# LED_Inducator.net
KiCad netlist of a schematic drawn in Altium Designer
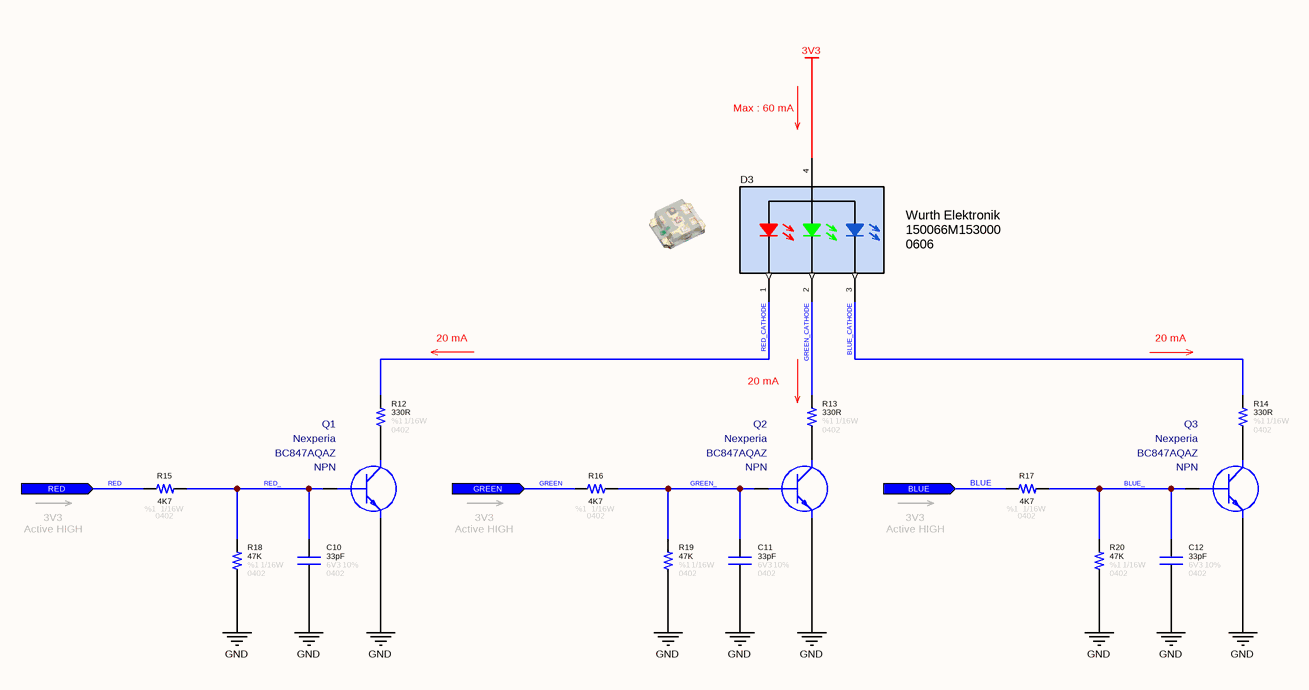
[diagram p0: LED Inducator.SchDoc]

(export (version "E")
  (design (tool "Eeschema 10.0.6"))
  (components
    (comp (ref "C10")
      (value "33pF")
      (footprint "CAPACITOR_0402")
      (description "Capacitor - 33pF [0402] (Ceramic)")
      (fields
        (field (name "MANUFACTURER PART NUMBER") "C0402C330J9RACAUTO")
        (field (name "TOLERANCE") "10%")
        (field (name "CASE") "0402")
        (field (name "VOLTAGE") "6V3")
      )
      (libsource (lib "Akkoyun") (part "Capacitor - 33pF [0402-6V3]"))
    )
    (comp (ref "C11")
      (value "33pF")
      (footprint "CAPACITOR_0402")
      (description "Capacitor - 33pF [0402] (Ceramic)")
      (fields
        (field (name "MANUFACTURER PART NUMBER") "C0402C330J9RACAUTO")
        (field (name "TOLERANCE") "10%")
        (field (name "CASE") "0402")
        (field (name "VOLTAGE") "6V3")
      )
      (libsource (lib "Akkoyun") (part "Capacitor - 33pF [0402-6V3]"))
    )
    (comp (ref "C12")
      (value "33pF")
      (footprint "CAPACITOR_0402")
      (description "Capacitor - 33pF [0402] (Ceramic)")
      (fields
        (field (name "MANUFACTURER PART NUMBER") "C0402C330J9RACAUTO")
        (field (name "TOLERANCE") "10%")
        (field (name "CASE") "0402")
        (field (name "VOLTAGE") "6V3")
      )
      (libsource (lib "Akkoyun") (part "Capacitor - 33pF [0402-6V3]"))
    )
    (comp (ref "D3")
      (value "~")
      (footprint "Wurth_0606")
      (description "LED RGB DIFFUSED SMD")
      (fields
        (field (name "MANUFACTURER NAME") "Wurth Elektronik")
        (field (name "MANUFACTURER PART NUMBER") "150066M153000")
        (field (name "CASE") "0606")
      )
      (libsource (lib "Akkoyun") (part "Diode - LED-RGB"))
    )
    (comp (ref "Q1")
      (value "~")
      (footprint "SOT1215")
      (description "Bipolar NPN Transistors")
      (fields
        (field (name "MANUFACTURER NAME") "Nexperia")
        (field (name "MANUFACTURER PART NUMBER") "BC847AQAZ")
        (field (name "POLARITY") "NPN")
      )
      (libsource (lib "Akkoyun") (part "Transistor - BC847"))
    )
    (comp (ref "Q2")
      (value "~")
      (footprint "SOT1215")
      (description "Bipolar NPN Transistors")
      (fields
        (field (name "MANUFACTURER NAME") "Nexperia")
        (field (name "MANUFACTURER PART NUMBER") "BC847AQAZ")
        (field (name "POLARITY") "NPN")
      )
      (libsource (lib "Akkoyun") (part "Transistor - BC847"))
    )
    (comp (ref "Q3")
      (value "~")
      (footprint "SOT1215")
      (description "Bipolar NPN Transistors")
      (fields
        (field (name "MANUFACTURER NAME") "Nexperia")
        (field (name "MANUFACTURER PART NUMBER") "BC847AQAZ")
        (field (name "POLARITY") "NPN")
      )
      (libsource (lib "Akkoyun") (part "Transistor - BC847"))
    )
    (comp (ref "R12")
      (value "330R")
      (footprint "RESISTOR_0402")
      (description "Thick Film Resistors - SMD 1/16 W 330 Ohm 1%")
      (fields
        (field (name "MANUFACTURER PART NUMBER") "CRCW0402330RFKED")
        (field (name "CASE") "0402")
        (field (name "TOLERANCE") "%1")
        (field (name "POWER") "1/16W")
      )
      (libsource (lib "Akkoyun") (part "Resistor - 330R [0402]"))
    )
    (comp (ref "R13")
      (value "330R")
      (footprint "RESISTOR_0402")
      (description "Thick Film Resistors - SMD 1/16 W 330 Ohm 1%")
      (fields
        (field (name "MANUFACTURER PART NUMBER") "CRCW0402330RFKED")
        (field (name "CASE") "0402")
        (field (name "TOLERANCE") "%1")
        (field (name "POWER") "1/16W")
      )
      (libsource (lib "Akkoyun") (part "Resistor - 330R [0402]"))
    )
    (comp (ref "R14")
      (value "330R")
      (footprint "RESISTOR_0402")
      (description "Thick Film Resistors - SMD 1/16 W 330 Ohm 1%")
      (fields
        (field (name "MANUFACTURER PART NUMBER") "CRCW0402330RFKED")
        (field (name "CASE") "0402")
        (field (name "TOLERANCE") "%1")
        (field (name "POWER") "1/16W")
      )
      (libsource (lib "Akkoyun") (part "Resistor - 330R [0402]"))
    )
    (comp (ref "R15")
      (value "4K7")
      (footprint "RESISTOR_0402")
      (description "Thick Film Resistors - SMD 1/16 W 4.7 KOhm 1%")
      (fields
        (field (name "MANUFACTURER PART NUMBER") "CRCW04024K70FKED")
        (field (name "TOLERANCE") "%1")
        (field (name "CASE") "0402")
        (field (name "POWER") "1/16W")
      )
      (libsource (lib "Akkoyun") (part "Resistor - 4K7 [0402]"))
    )
    (comp (ref "R16")
      (value "4K7")
      (footprint "RESISTOR_0402")
      (description "Thick Film Resistors - SMD 1/16 W 4.7 KOhm 1%")
      (fields
        (field (name "MANUFACTURER PART NUMBER") "CRCW04024K70FKED")
        (field (name "TOLERANCE") "%1")
        (field (name "CASE") "0402")
        (field (name "POWER") "1/16W")
      )
      (libsource (lib "Akkoyun") (part "Resistor - 4K7 [0402]"))
    )
    (comp (ref "R17")
      (value "4K7")
      (footprint "RESISTOR_0402")
      (description "Thick Film Resistors - SMD 1/16 W 4.7 KOhm 1%")
      (fields
        (field (name "MANUFACTURER PART NUMBER") "CRCW04024K70FKED")
        (field (name "TOLERANCE") "%1")
        (field (name "CASE") "0402")
        (field (name "POWER") "1/16W")
      )
      (libsource (lib "Akkoyun") (part "Resistor - 4K7 [0402]"))
    )
    (comp (ref "R18")
      (value "47K")
      (footprint "RESISTOR_0402")
      (description "Thick Film Resistors - SMD 1/16 W 47 KOhm 1%")
      (fields
        (field (name "MANUFACTURER PART NUMBER") "CRCW040247K0FKED")
        (field (name "TOLERANCE") "%1")
        (field (name "CASE") "0402")
        (field (name "POWER") "1/16W")
      )
      (libsource (lib "Akkoyun") (part "Resistor - 47K [0402]"))
    )
    (comp (ref "R19")
      (value "47K")
      (footprint "RESISTOR_0402")
      (description "Thick Film Resistors - SMD 1/16 W 47 KOhm 1%")
      (fields
        (field (name "MANUFACTURER PART NUMBER") "CRCW040247K0FKED")
        (field (name "TOLERANCE") "%1")
        (field (name "CASE") "0402")
        (field (name "POWER") "1/16W")
      )
      (libsource (lib "Akkoyun") (part "Resistor - 47K [0402]"))
    )
    (comp (ref "R20")
      (value "47K")
      (footprint "RESISTOR_0402")
      (description "Thick Film Resistors - SMD 1/16 W 47 KOhm 1%")
      (fields
        (field (name "MANUFACTURER PART NUMBER") "CRCW040247K0FKED")
        (field (name "TOLERANCE") "%1")
        (field (name "CASE") "0402")
        (field (name "POWER") "1/16W")
      )
      (libsource (lib "Akkoyun") (part "Resistor - 47K [0402]"))
    )
  )
  (nets
    (net (code "1") (name "/BLUE") (class "Default")
      (node (ref "R17") (pin "2") (pinfunction "2_2") (pintype "passive"))
    )
    (net (code "2") (name "/BLUE_") (class "Default")
      (node (ref "C12") (pin "2") (pinfunction "2_2") (pintype "passive"))
      (node (ref "Q3") (pin "1") (pinfunction "B_1") (pintype "passive"))
      (node (ref "R17") (pin "1") (pinfunction "1_1") (pintype "passive"))
      (node (ref "R20") (pin "2") (pinfunction "2_2") (pintype "passive"))
    )
    (net (code "3") (name "/BLUE_CATHODE") (class "Default")
      (node (ref "D3") (pin "3") (pinfunction "3_3") (pintype "output"))
      (node (ref "R14") (pin "2") (pinfunction "2_2") (pintype "passive"))
    )
    (net (code "4") (name "/GREEN") (class "Default")
      (node (ref "R16") (pin "2") (pinfunction "2_2") (pintype "passive"))
    )
    (net (code "5") (name "/GREEN_") (class "Default")
      (node (ref "C11") (pin "2") (pinfunction "2_2") (pintype "passive"))
      (node (ref "Q2") (pin "1") (pinfunction "B_1") (pintype "passive"))
      (node (ref "R16") (pin "1") (pinfunction "1_1") (pintype "passive"))
      (node (ref "R19") (pin "2") (pinfunction "2_2") (pintype "passive"))
    )
    (net (code "6") (name "/GREEN_CATHODE") (class "Default")
      (node (ref "D3") (pin "2") (pinfunction "2_2") (pintype "output"))
      (node (ref "R13") (pin "2") (pinfunction "2_2") (pintype "passive"))
    )
    (net (code "7") (name "/RED") (class "Default")
      (node (ref "R15") (pin "2") (pinfunction "2_2") (pintype "passive"))
    )
    (net (code "8") (name "/RED_") (class "Default")
      (node (ref "C10") (pin "2") (pinfunction "2_2") (pintype "passive"))
      (node (ref "Q1") (pin "1") (pinfunction "B_1") (pintype "passive"))
      (node (ref "R15") (pin "1") (pinfunction "1_1") (pintype "passive"))
      (node (ref "R18") (pin "2") (pinfunction "2_2") (pintype "passive"))
    )
    (net (code "9") (name "/RED_CATHODE") (class "Default")
      (node (ref "D3") (pin "1") (pinfunction "1_1") (pintype "output"))
      (node (ref "R12") (pin "2") (pinfunction "2_2") (pintype "passive"))
    )
    (net (code "10") (name "3V3") (class "Default")
      (node (ref "D3") (pin "4") (pinfunction "4_4") (pintype "power_in"))
    )
    (net (code "11") (name "GND") (class "Default")
      (node (ref "C10") (pin "1") (pinfunction "1_1") (pintype "passive"))
      (node (ref "C11") (pin "1") (pinfunction "1_1") (pintype "passive"))
      (node (ref "C12") (pin "1") (pinfunction "1_1") (pintype "passive"))
      (node (ref "Q1") (pin "2") (pinfunction "E_2") (pintype "passive"))
      (node (ref "Q2") (pin "2") (pinfunction "E_2") (pintype "passive"))
      (node (ref "Q3") (pin "2") (pinfunction "E_2") (pintype "passive"))
      (node (ref "R18") (pin "1") (pinfunction "1_1") (pintype "passive"))
      (node (ref "R19") (pin "1") (pinfunction "1_1") (pintype "passive"))
      (node (ref "R20") (pin "1") (pinfunction "1_1") (pintype "passive"))
    )
    (net (code "12") (name "Net-(Q1-C)") (class "Default")
      (node (ref "Q1") (pin "3") (pinfunction "C_3") (pintype "passive"))
      (node (ref "R12") (pin "1") (pinfunction "1_1") (pintype "passive"))
    )
    (net (code "13") (name "Net-(Q2-C)") (class "Default")
      (node (ref "Q2") (pin "3") (pinfunction "C_3") (pintype "passive"))
      (node (ref "R13") (pin "1") (pinfunction "1_1") (pintype "passive"))
    )
    (net (code "14") (name "Net-(Q3-C)") (class "Default")
      (node (ref "Q3") (pin "3") (pinfunction "C_3") (pintype "passive"))
      (node (ref "R14") (pin "1") (pinfunction "1_1") (pintype "passive"))
    )
  )
)
